# nRF_prog_vusb_3V3.net
KiCad netlist of a schematic drawn in EAGLE
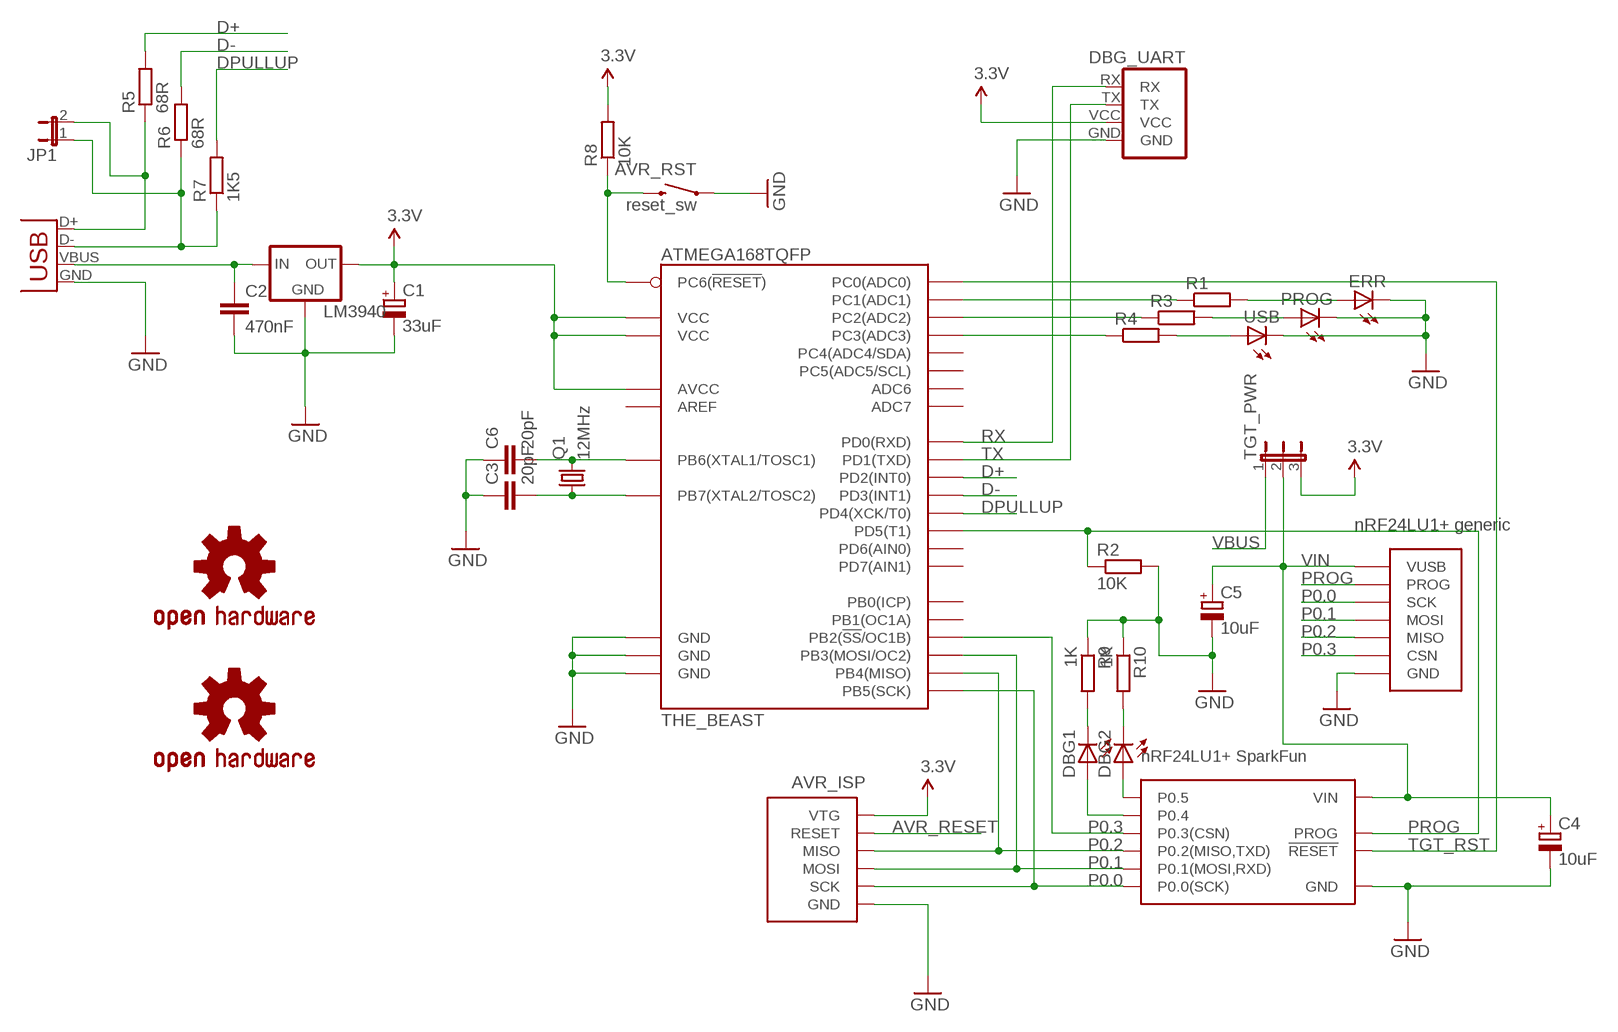
[diagram p0: schematic, sheet 1]

(export (version "E")
  (design (tool "Eeschema 10.0.6"))
  (components
    (comp (ref "AVR_ISP")
      (value "AVR-ISP-6SMALL_FP")
      (footprint "eagle-import:AVR-ISP-6-SMALL-FP")
      (libsource (lib "eagle-import") (part "AVR-ISP-6SMALL_FP"))
    )
    (comp (ref "AVR_RST")
      (value "reset_sw")
      (footprint "eagle-import:TACTILE_SWITCH_SMD")
      (libsource (lib "eagle-import") (part "SWITCH-MOMENTARY-2SMD"))
    )
    (comp (ref "C1")
      (value "33uF")
      (footprint "eagle-import:SMC_B")
      (libsource (lib "eagle-import") (part "CPOL-EUSMCB"))
    )
    (comp (ref "C2")
      (value "470nF")
      (footprint "eagle-import:C0805K")
      (libsource (lib "eagle-import") (part "C-EUC0805K"))
    )
    (comp (ref "C3")
      (value "20pF")
      (footprint "eagle-import:C0805")
      (libsource (lib "eagle-import") (part "C-EUC0805"))
    )
    (comp (ref "C4")
      (value "10uF")
      (footprint "eagle-import:SMC_B")
      (libsource (lib "eagle-import") (part "CPOL-EUSMCB"))
    )
    (comp (ref "C5")
      (value "10uF")
      (footprint "eagle-import:SMC_B")
      (libsource (lib "eagle-import") (part "CPOL-EUSMCB"))
    )
    (comp (ref "C6")
      (value "20pF")
      (footprint "eagle-import:C0805")
      (libsource (lib "eagle-import") (part "C-EUC0805"))
    )
    (comp (ref "DBG1")
      (value "LEDCHIPLED_0805")
      (footprint "eagle-import:CHIPLED_0805")
      (libsource (lib "eagle-import") (part "LEDCHIPLED_0805"))
    )
    (comp (ref "DBG2")
      (value "LEDCHIPLED_0805")
      (footprint "eagle-import:CHIPLED_0805")
      (libsource (lib "eagle-import") (part "LEDCHIPLED_0805"))
    )
    (comp (ref "DBG_UART")
      (value "UART_PORT")
      (footprint "eagle-import:UART_PORT")
      (libsource (lib "eagle-import") (part "UART_PORT"))
    )
    (comp (ref "ERR")
      (value "LEDCHIPLED_0805")
      (footprint "eagle-import:CHIPLED_0805")
      (libsource (lib "eagle-import") (part "LEDCHIPLED_0805"))
    )
    (comp (ref "JP1")
      (value "JP1E")
      (footprint "eagle-import:JP1")
      (libsource (lib "eagle-import") (part "JP1E"))
    )
    (comp (ref "LM3940")
      (value "LM3940")
      (footprint "eagle-import:SOT223")
      (libsource (lib "eagle-import") (part "LM3940"))
    )
    (comp (ref "LU1+_GENERIC")
      (value "NRF24LU1P_GENERIC")
      (footprint "eagle-import:NRF24LU1P_GENERIC")
      (libsource (lib "eagle-import") (part "NRF24LU1P_GENERIC"))
    )
    (comp (ref "LU1+_SPARKFUN")
      (value "NRF24LU1P_SPARKFUN_BREAKOUT")
      (footprint "eagle-import:NRF24LU+_SPARKFUN_BREAKOUT")
      (libsource (lib "eagle-import") (part "NRF24LU1P_SPARKFUN_BREAKOUT"))
    )
    (comp (ref "PROG")
      (value "LEDCHIPLED_0805")
      (footprint "eagle-import:CHIPLED_0805")
      (libsource (lib "eagle-import") (part "LEDCHIPLED_0805"))
    )
    (comp (ref "Q1")
      (value "12MHz")
      (footprint "eagle-import:QUARTZ")
      (libsource (lib "eagle-import") (part "CRYSTALHC49U-V"))
    )
    (comp (ref "R1")
      (value "R-EU_M0805")
      (footprint "eagle-import:M0805")
      (libsource (lib "eagle-import") (part "R-EU_M0805"))
    )
    (comp (ref "R2")
      (value "10K")
      (footprint "eagle-import:M0805")
      (libsource (lib "eagle-import") (part "R-EU_M0805"))
    )
    (comp (ref "R3")
      (value "R-EU_M0805")
      (footprint "eagle-import:M0805")
      (libsource (lib "eagle-import") (part "R-EU_M0805"))
    )
    (comp (ref "R4")
      (value "R-EU_M0805")
      (footprint "eagle-import:M0805")
      (libsource (lib "eagle-import") (part "R-EU_M0805"))
    )
    (comp (ref "R5")
      (value "68R")
      (footprint "eagle-import:M0805")
      (libsource (lib "eagle-import") (part "R-EU_M0805"))
    )
    (comp (ref "R6")
      (value "68R")
      (footprint "eagle-import:M0805")
      (libsource (lib "eagle-import") (part "R-EU_M0805"))
    )
    (comp (ref "R7")
      (value "1K5")
      (footprint "eagle-import:M0805")
      (libsource (lib "eagle-import") (part "R-EU_M0805"))
    )
    (comp (ref "R8")
      (value "10K")
      (footprint "eagle-import:M0805")
      (libsource (lib "eagle-import") (part "R-EU_M0805"))
    )
    (comp (ref "R9")
      (value "1K")
      (footprint "eagle-import:M0805")
      (libsource (lib "eagle-import") (part "R-EU_M0805"))
    )
    (comp (ref "R10")
      (value "1K")
      (footprint "eagle-import:M0805")
      (libsource (lib "eagle-import") (part "R-EU_M0805"))
    )
    (comp (ref "TGT_PWR")
      (value "JP2E")
      (footprint "eagle-import:JP2")
      (libsource (lib "eagle-import") (part "JP2E"))
    )
    (comp (ref "THE_BEAST")
      (value "ATMEGA168TQFP")
      (footprint "eagle-import:TQFP32-08")
      (libsource (lib "eagle-import") (part "ATMEGA168TQFP"))
    )
    (comp (ref "U$1")
      (value "OSHW-LOGOM")
      (footprint "eagle-import:OSHW-LOGO-M")
      (libsource (lib "eagle-import") (part "OSHW-LOGOM"))
    )
    (comp (ref "U$2")
      (value "OSHW-LOGOL")
      (footprint "eagle-import:OSHW-LOGO-L")
      (libsource (lib "eagle-import") (part "OSHW-LOGOL"))
    )
    (comp (ref "USB")
      (value "LEDCHIPLED_0805")
      (footprint "eagle-import:CHIPLED_0805")
      (libsource (lib "eagle-import") (part "LEDCHIPLED_0805"))
    )
    (comp (ref "USB-B")
      (value "USBPTH")
      (footprint "eagle-import:USB-B-PTH")
      (libsource (lib "eagle-import") (part "USBPTH"))
    )
  )
  (nets
    (net (code "1") (name "/AVR_RESET") (class "Default")
      (node (ref "AVR_ISP") (pin "RESET") (pinfunction "RESET_RESET") (pintype "passive"))
      (node (ref "AVR_RST") (pin "3") (pinfunction "2_3") (pintype "passive"))
      (node (ref "R8") (pin "1") (pinfunction "1_1") (pintype "passive"))
      (node (ref "THE_BEAST") (pin "29") (pinfunction "PC6(~{RESET})_29") (pintype "bidirectional"))
    )
    (net (code "2") (name "/D+") (class "Default")
      (node (ref "R5") (pin "2") (pinfunction "2_2") (pintype "passive"))
      (node (ref "THE_BEAST") (pin "32") (pinfunction "PD2(INT0)_32") (pintype "bidirectional"))
    )
    (net (code "3") (name "/D-") (class "Default")
      (node (ref "R6") (pin "2") (pinfunction "2_2") (pintype "passive"))
      (node (ref "THE_BEAST") (pin "1") (pinfunction "PD3(INT1)_1") (pintype "bidirectional"))
    )
    (net (code "4") (name "/DPULLUP") (class "Default")
      (node (ref "R7") (pin "2") (pinfunction "2_2") (pintype "passive"))
      (node (ref "THE_BEAST") (pin "2") (pinfunction "PD4(XCK/T0)_2") (pintype "bidirectional"))
    )
    (net (code "5") (name "/P0.0") (class "Default")
      (node (ref "AVR_ISP") (pin "SCK") (pinfunction "SCK_SCK") (pintype "passive"))
      (node (ref "LU1+_GENERIC") (pin "SCK") (pinfunction "SCK_SCK") (pintype "bidirectional"))
      (node (ref "LU1+_SPARKFUN") (pin "P0.0") (pinfunction "P0.0(SCK)_P0.0") (pintype "bidirectional"))
      (node (ref "THE_BEAST") (pin "17") (pinfunction "PB5(SCK)_17") (pintype "bidirectional"))
    )
    (net (code "6") (name "/P0.1") (class "Default")
      (node (ref "AVR_ISP") (pin "MOSI") (pinfunction "MOSI_MOSI") (pintype "passive"))
      (node (ref "LU1+_GENERIC") (pin "MOSI") (pinfunction "MOSI_MOSI") (pintype "bidirectional"))
      (node (ref "LU1+_SPARKFUN") (pin "P0.1") (pinfunction "P0.1(MOSI,RXD)_P0.1") (pintype "bidirectional"))
      (node (ref "THE_BEAST") (pin "15") (pinfunction "PB3(MOSI/OC2)_15") (pintype "bidirectional"))
    )
    (net (code "7") (name "/P0.2") (class "Default")
      (node (ref "AVR_ISP") (pin "MISO") (pinfunction "MISO_MISO") (pintype "passive"))
      (node (ref "LU1+_GENERIC") (pin "MISO") (pinfunction "MISO_MISO") (pintype "bidirectional"))
      (node (ref "LU1+_SPARKFUN") (pin "P0.2") (pinfunction "P0.2(MISO,TXD)_P0.2") (pintype "bidirectional"))
      (node (ref "THE_BEAST") (pin "16") (pinfunction "PB4(MISO)_16") (pintype "bidirectional"))
    )
    (net (code "8") (name "/P0.3") (class "Default")
      (node (ref "LU1+_GENERIC") (pin "CSN") (pinfunction "CSN_CSN") (pintype "bidirectional"))
      (node (ref "LU1+_SPARKFUN") (pin "P0.3") (pinfunction "P0.3(CSN)_P0.3") (pintype "bidirectional"))
      (node (ref "THE_BEAST") (pin "14") (pinfunction "PB2(~{SS}/OC1B)_14") (pintype "bidirectional"))
    )
    (net (code "9") (name "/PROG") (class "Default")
      (node (ref "LU1+_GENERIC") (pin "PROG") (pinfunction "PROG_PROG") (pintype "bidirectional"))
      (node (ref "LU1+_SPARKFUN") (pin "PROG") (pinfunction "PROG_PROG") (pintype "bidirectional"))
      (node (ref "R2") (pin "1") (pinfunction "1_1") (pintype "passive"))
      (node (ref "THE_BEAST") (pin "9") (pinfunction "PD5(T1)_9") (pintype "bidirectional"))
    )
    (net (code "10") (name "/RX") (class "Default")
      (node (ref "DBG_UART") (pin "RX") (pinfunction "RX_RX") (pintype "passive"))
      (node (ref "THE_BEAST") (pin "30") (pinfunction "PD0(RXD)_30") (pintype "bidirectional"))
    )
    (net (code "11") (name "/TGT_RST") (class "Default")
      (node (ref "LU1+_SPARKFUN") (pin "RESET") (pinfunction "~{RESET}_RESET") (pintype "bidirectional"))
      (node (ref "THE_BEAST") (pin "23") (pinfunction "PC0(ADC0)_23") (pintype "bidirectional"))
    )
    (net (code "12") (name "/TX") (class "Default")
      (node (ref "DBG_UART") (pin "TX") (pinfunction "TX_TX") (pintype "passive"))
      (node (ref "THE_BEAST") (pin "31") (pinfunction "PD1(TXD)_31") (pintype "bidirectional"))
    )
    (net (code "13") (name "/VBUS") (class "Default")
      (node (ref "C2") (pin "1") (pinfunction "1_1") (pintype "passive"))
      (node (ref "LM3940") (pin "1") (pinfunction "IN_1") (pintype "input"))
      (node (ref "TGT_PWR") (pin "1") (pinfunction "1_1") (pintype "passive"))
      (node (ref "USB-B") (pin "VBUS") (pinfunction "VBUS_VBUS") (pintype "bidirectional"))
    )
    (net (code "14") (name "/VIN") (class "Default")
      (node (ref "C4") (pin "+") (pinfunction "+_+") (pintype "passive"))
      (node (ref "C5") (pin "+") (pinfunction "+_+") (pintype "passive"))
      (node (ref "LU1+_GENERIC") (pin "VUSB") (pinfunction "VUSB_VUSB") (pintype "power_in"))
      (node (ref "LU1+_SPARKFUN") (pin "VIN") (pinfunction "VIN_VIN") (pintype "bidirectional"))
      (node (ref "TGT_PWR") (pin "2") (pinfunction "2_2") (pintype "passive"))
    )
    (net (code "15") (name "3.3V") (class "Default")
      (node (ref "AVR_ISP") (pin "VCC") (pinfunction "VTG_VCC") (pintype "passive"))
      (node (ref "C1") (pin "+") (pinfunction "+_+") (pintype "passive"))
      (node (ref "DBG_UART") (pin "VCC") (pinfunction "VCC_VCC") (pintype "passive"))
      (node (ref "LM3940") (pin "3") (pinfunction "OUT_3") (pintype "output"))
      (node (ref "R8") (pin "2") (pinfunction "2_2") (pintype "passive"))
      (node (ref "TGT_PWR") (pin "3") (pinfunction "3_3") (pintype "passive"))
      (node (ref "THE_BEAST") (pin "18") (pinfunction "AVCC_18") (pintype "input"))
      (node (ref "THE_BEAST") (pin "4") (pinfunction "VCC_4") (pintype "power_in"))
      (node (ref "THE_BEAST") (pin "6") (pinfunction "VCC_6") (pintype "power_in"))
    )
    (net (code "16") (name "GND") (class "Default")
      (node (ref "AVR_ISP") (pin "GND") (pinfunction "GND_GND") (pintype "passive"))
      (node (ref "AVR_RST") (pin "1") (pinfunction "1_1") (pintype "passive"))
      (node (ref "C1") (pin "-") (pinfunction "-_-") (pintype "passive"))
      (node (ref "C2") (pin "2") (pinfunction "2_2") (pintype "passive"))
      (node (ref "C3") (pin "1") (pinfunction "1_1") (pintype "passive"))
      (node (ref "C4") (pin "-") (pinfunction "-_-") (pintype "passive"))
      (node (ref "C5") (pin "-") (pinfunction "-_-") (pintype "passive"))
      (node (ref "C6") (pin "1") (pinfunction "1_1") (pintype "passive"))
      (node (ref "DBG_UART") (pin "GND") (pinfunction "GND_GND") (pintype "passive"))
      (node (ref "ERR") (pin "C") (pinfunction "C_C") (pintype "passive"))
      (node (ref "LM3940") (pin "2") (pinfunction "GND_2") (pintype "input"))
      (node (ref "LM3940") (pin "4") (pinfunction "GND_4") (pintype "input"))
      (node (ref "LU1+_GENERIC") (pin "GND") (pinfunction "GND_GND") (pintype "power_in"))
      (node (ref "LU1+_SPARKFUN") (pin "GND") (pinfunction "GND_GND") (pintype "bidirectional"))
      (node (ref "PROG") (pin "C") (pinfunction "C_C") (pintype "passive"))
      (node (ref "R10") (pin "1") (pinfunction "1_1") (pintype "passive"))
      (node (ref "R2") (pin "2") (pinfunction "2_2") (pintype "passive"))
      (node (ref "R9") (pin "1") (pinfunction "1_1") (pintype "passive"))
      (node (ref "THE_BEAST") (pin "21") (pinfunction "GND_21") (pintype "power_in"))
      (node (ref "THE_BEAST") (pin "3") (pinfunction "GND_3") (pintype "power_in"))
      (node (ref "THE_BEAST") (pin "5") (pinfunction "GND_5") (pintype "power_in"))
      (node (ref "USB") (pin "C") (pinfunction "C_C") (pintype "passive"))
      (node (ref "USB-B") (pin "GND") (pinfunction "GND_GND") (pintype "bidirectional"))
    )
    (net (code "17") (name "Net-(DBG1-PadA)") (class "Default")
      (node (ref "DBG1") (pin "A") (pinfunction "A_A") (pintype "passive"))
      (node (ref "LU1+_SPARKFUN") (pin "P0.4") (pinfunction "P0.4_P0.4") (pintype "bidirectional"))
    )
    (net (code "18") (name "Net-(DBG1-PadC)") (class "Default")
      (node (ref "DBG1") (pin "C") (pinfunction "C_C") (pintype "passive"))
      (node (ref "R9") (pin "2") (pinfunction "2_2") (pintype "passive"))
    )
    (net (code "19") (name "Net-(DBG2-PadA)") (class "Default")
      (node (ref "DBG2") (pin "A") (pinfunction "A_A") (pintype "passive"))
      (node (ref "LU1+_SPARKFUN") (pin "P0.5") (pinfunction "P0.5_P0.5") (pintype "bidirectional"))
    )
    (net (code "20") (name "Net-(DBG2-PadC)") (class "Default")
      (node (ref "DBG2") (pin "C") (pinfunction "C_C") (pintype "passive"))
      (node (ref "R10") (pin "2") (pinfunction "2_2") (pintype "passive"))
    )
    (net (code "21") (name "Net-(ERR-PadA)") (class "Default")
      (node (ref "ERR") (pin "A") (pinfunction "A_A") (pintype "passive"))
      (node (ref "R1") (pin "2") (pinfunction "2_2") (pintype "passive"))
    )
    (net (code "22") (name "Net-(JP1-Pad1)") (class "Default")
      (node (ref "JP1") (pin "1") (pinfunction "1_1") (pintype "passive"))
      (node (ref "R6") (pin "1") (pinfunction "1_1") (pintype "passive"))
      (node (ref "R7") (pin "1") (pinfunction "1_1") (pintype "passive"))
      (node (ref "USB-B") (pin "D-") (pinfunction "D-_D-") (pintype "bidirectional"))
    )
    (net (code "23") (name "Net-(JP1-Pad2)") (class "Default")
      (node (ref "JP1") (pin "2") (pinfunction "2_2") (pintype "passive"))
      (node (ref "R5") (pin "1") (pinfunction "1_1") (pintype "passive"))
      (node (ref "USB-B") (pin "D+") (pinfunction "D+_D+") (pintype "bidirectional"))
    )
    (net (code "24") (name "Net-(PROG-PadA)") (class "Default")
      (node (ref "PROG") (pin "A") (pinfunction "A_A") (pintype "passive"))
      (node (ref "R3") (pin "2") (pinfunction "2_2") (pintype "passive"))
    )
    (net (code "25") (name "Net-(R4-Pad2)") (class "Default")
      (node (ref "R4") (pin "2") (pinfunction "2_2") (pintype "passive"))
      (node (ref "USB") (pin "A") (pinfunction "A_A") (pintype "passive"))
    )
    (net (code "26") (name "Net-(THE_BEAST-PB6(XTAL1{slash}TOSC1))") (class "Default")
      (node (ref "C6") (pin "2") (pinfunction "2_2") (pintype "passive"))
      (node (ref "Q1") (pin "2") (pinfunction "2_2") (pintype "passive"))
      (node (ref "THE_BEAST") (pin "7") (pinfunction "PB6(XTAL1/TOSC1)_7") (pintype "bidirectional"))
    )
    (net (code "27") (name "Net-(THE_BEAST-PB7(XTAL2{slash}TOSC2))") (class "Default")
      (node (ref "C3") (pin "2") (pinfunction "2_2") (pintype "passive"))
      (node (ref "Q1") (pin "1") (pinfunction "1_1") (pintype "passive"))
      (node (ref "THE_BEAST") (pin "8") (pinfunction "PB7(XTAL2/TOSC2)_8") (pintype "bidirectional"))
    )
    (net (code "28") (name "Net-(THE_BEAST-PC1(ADC1))") (class "Default")
      (node (ref "R1") (pin "1") (pinfunction "1_1") (pintype "passive"))
      (node (ref "THE_BEAST") (pin "24") (pinfunction "PC1(ADC1)_24") (pintype "bidirectional"))
    )
    (net (code "29") (name "Net-(THE_BEAST-PC2(ADC2))") (class "Default")
      (node (ref "R3") (pin "1") (pinfunction "1_1") (pintype "passive"))
      (node (ref "THE_BEAST") (pin "25") (pinfunction "PC2(ADC2)_25") (pintype "bidirectional"))
    )
    (net (code "30") (name "Net-(THE_BEAST-PC3(ADC3))") (class "Default")
      (node (ref "R4") (pin "1") (pinfunction "1_1") (pintype "passive"))
      (node (ref "THE_BEAST") (pin "26") (pinfunction "PC3(ADC3)_26") (pintype "bidirectional"))
    )
    (net (code "31") (name "unconnected-(THE_BEAST-ADC6-Pad19)") (class "Default")
      (node (ref "THE_BEAST") (pin "19") (pinfunction "ADC6_19") (pintype "bidirectional"))
    )
    (net (code "32") (name "unconnected-(THE_BEAST-ADC7-Pad22)") (class "Default")
      (node (ref "THE_BEAST") (pin "22") (pinfunction "ADC7_22") (pintype "bidirectional"))
    )
    (net (code "33") (name "unconnected-(THE_BEAST-AREF-Pad20)") (class "Default")
      (node (ref "THE_BEAST") (pin "20") (pinfunction "AREF_20") (pintype "input"))
    )
    (net (code "34") (name "unconnected-(THE_BEAST-PB0(ICP)-Pad12)") (class "Default")
      (node (ref "THE_BEAST") (pin "12") (pinfunction "PB0(ICP)_12") (pintype "bidirectional"))
    )
    (net (code "35") (name "unconnected-(THE_BEAST-PB1(OC1A)-Pad13)") (class "Default")
      (node (ref "THE_BEAST") (pin "13") (pinfunction "PB1(OC1A)_13") (pintype "bidirectional"))
    )
    (net (code "36") (name "unconnected-(THE_BEAST-PC4(ADC4{slash}SDA)-Pad27)") (class "Default")
      (node (ref "THE_BEAST") (pin "27") (pinfunction "PC4(ADC4/SDA)_27") (pintype "bidirectional"))
    )
    (net (code "37") (name "unconnected-(THE_BEAST-PC5(ADC5{slash}SCL)-Pad28)") (class "Default")
      (node (ref "THE_BEAST") (pin "28") (pinfunction "PC5(ADC5/SCL)_28") (pintype "bidirectional"))
    )
    (net (code "38") (name "unconnected-(THE_BEAST-PD6(AIN0)-Pad10)") (class "Default")
      (node (ref "THE_BEAST") (pin "10") (pinfunction "PD6(AIN0)_10") (pintype "bidirectional"))
    )
    (net (code "39") (name "unconnected-(THE_BEAST-PD7(AIN1)-Pad11)") (class "Default")
      (node (ref "THE_BEAST") (pin "11") (pinfunction "PD7(AIN1)_11") (pintype "bidirectional"))
    )
  )
)
